# USBCONN_A_short_noTVS.net
KiCad netlist of a schematic drawn in Altium Designer
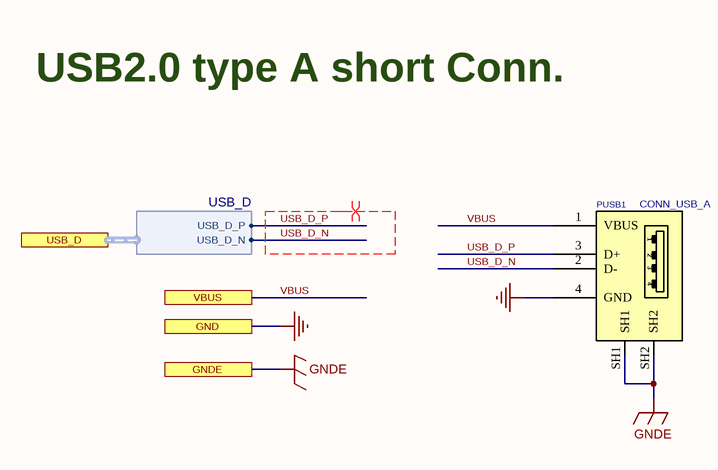
[diagram p0: USBCONN_A_short_noTVS.SchDoc]

(export (version "E")
  (design (tool "Eeschema 10.0.6"))
  (components
    (comp (ref "PUSB1")
      (value "CONN_USB_A")
      (footprint "USB_A_REC_RA_THD_S")
      (description "CONN, USB, A, RECEPTACLE, R/A, THD")
      (fields (field (name "MANF_P#") "USB1125"))
      (libsource (lib "conn_usb") (part "CONN_USB_A_REC_RA_THD_SHORT"))
    )
  )
  (nets
    (net (code "2") (name "/USB_D_N") (class "Default")
      (node (ref "PUSB1") (pin "2") (pinfunction "D-_2") (pintype "passive"))
    )
    (net (code "3") (name "/USB_D_P") (class "Default")
      (node (ref "PUSB1") (pin "3") (pinfunction "D+_3") (pintype "passive"))
    )
    (net (code "4") (name "/VBUS") (class "Default")
      (node (ref "PUSB1") (pin "1") (pinfunction "VBUS_1") (pintype "passive"))
    )
    (net (code "6") (name "GND") (class "Default")
      (node (ref "PUSB1") (pin "4") (pinfunction "GND_4") (pintype "passive"))
    )
    (net (code "7") (name "GNDE") (class "Default")
      (node (ref "PUSB1") (pin "SH1") (pinfunction "SH1_SH1") (pintype "passive"))
      (node (ref "PUSB1") (pin "SH2") (pinfunction "SH2_SH2") (pintype "passive"))
    )
  )
)
